# Sema.net
KiCad netlist of a schematic drawn in Altium Designer
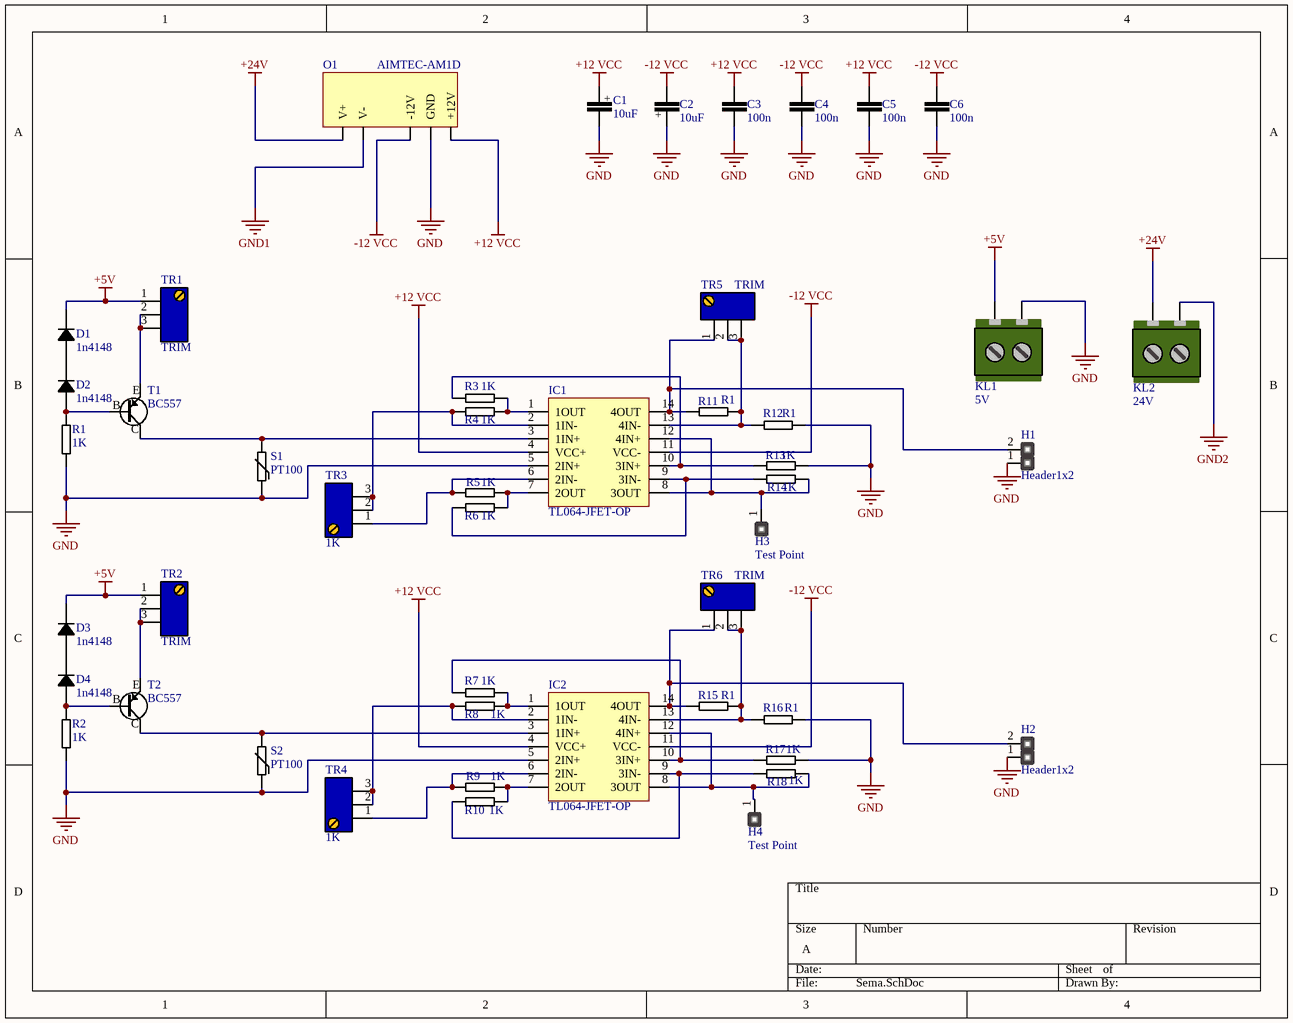
[diagram p0: Sema.SchDoc]

(export (version "E")
  (design (tool "Eeschema 10.0.6"))
  (components
    (comp (ref "C1") (value "10uF") (footprint "C2-Small") (libsource (lib "KILEX LIB SCH") (part "C2")))
    (comp (ref "C2") (value "10uF") (footprint "C2-Small") (libsource (lib "KILEX LIB SCH") (part "C2")))
    (comp (ref "C3")
      (value "100n")
      (footprint "C1(Ceramic)Small")
      (libsource (lib "KILEX LIB SCH") (part "C1"))
    )
    (comp (ref "C4")
      (value "100n")
      (footprint "C1(Ceramic)Small")
      (libsource (lib "KILEX LIB SCH") (part "C1"))
    )
    (comp (ref "C5")
      (value "100n")
      (footprint "C1(Ceramic)Small")
      (libsource (lib "KILEX LIB SCH") (part "C1"))
    )
    (comp (ref "C6")
      (value "100n")
      (footprint "C1(Ceramic)Small")
      (libsource (lib "KILEX LIB SCH") (part "C1"))
    )
    (comp (ref "D1")
      (value "1n4148")
      (footprint "D1(minimelf)")
      (libsource (lib "KILEX LIB SCH") (part "D1"))
    )
    (comp (ref "D2")
      (value "1n4148")
      (footprint "D1(minimelf)")
      (libsource (lib "KILEX LIB SCH") (part "D1"))
    )
    (comp (ref "D3")
      (value "1n4148")
      (footprint "D1(minimelf)")
      (libsource (lib "KILEX LIB SCH") (part "D1"))
    )
    (comp (ref "D4")
      (value "1n4148")
      (footprint "D1(minimelf)")
      (libsource (lib "KILEX LIB SCH") (part "D1"))
    )
    (comp (ref "H1")
      (value "Header1x2")
      (footprint "Header1x2")
      (libsource (lib "KILEX LIB SCH") (part "Header1x2"))
    )
    (comp (ref "H2")
      (value "Header1x2")
      (footprint "Header1x2")
      (libsource (lib "KILEX LIB SCH") (part "Header1x2"))
    )
    (comp (ref "H3") (value "Test Point") (footprint "H1x1") (libsource (lib "KILEX LIB SCH") (part "H1x1")))
    (comp (ref "H4") (value "Test Point") (footprint "H1x1") (libsource (lib "KILEX LIB SCH") (part "H1x1")))
    (comp (ref "IC1")
      (value "TL064-JFET-OP")
      (footprint "DIP14")
      (libsource (lib "KILEX LIB SCH") (part "TL064-JFET-OP"))
    )
    (comp (ref "IC2")
      (value "TL064-JFET-OP")
      (footprint "DIP14")
      (libsource (lib "KILEX LIB SCH") (part "TL064-JFET-OP"))
    )
    (comp (ref "KL1") (value "5V") (footprint "Klema") (libsource (lib "KILEX LIB SCH") (part "Klema")))
    (comp (ref "KL2") (value "24V") (footprint "Klema") (libsource (lib "KILEX LIB SCH") (part "Klema")))
    (comp (ref "O1")
      (value "AIMTEC-AM1D")
      (footprint "Aimtec-AM1D")
      (libsource (lib "KILEX LIB SCH") (part "AIMTEC-AM1D"))
    )
    (comp (ref "R1") (value "1K") (footprint "R 0805") (libsource (lib "KILEX LIB SCH") (part "R1")))
    (comp (ref "R2") (value "1K") (footprint "R 0805") (libsource (lib "KILEX LIB SCH") (part "R1")))
    (comp (ref "R3") (value "1K") (footprint "R 0805") (libsource (lib "KILEX LIB SCH") (part "R1")))
    (comp (ref "R4") (value "1K") (footprint "R 0805") (libsource (lib "KILEX LIB SCH") (part "R1")))
    (comp (ref "R5") (value "1K") (footprint "R 0805") (libsource (lib "KILEX LIB SCH") (part "R1")))
    (comp (ref "R6") (value "1K") (footprint "R 0805") (libsource (lib "KILEX LIB SCH") (part "R1")))
    (comp (ref "R7") (value "1K") (footprint "R 0805") (libsource (lib "KILEX LIB SCH") (part "R1")))
    (comp (ref "R8") (value "1K") (footprint "R 0805") (libsource (lib "KILEX LIB SCH") (part "R1")))
    (comp (ref "R9") (value "1K") (footprint "R 0805") (libsource (lib "KILEX LIB SCH") (part "R1")))
    (comp (ref "R10") (value "1K") (footprint "R 0805") (libsource (lib "KILEX LIB SCH") (part "R1")))
    (comp (ref "R11") (value "R1") (footprint "R 0805") (libsource (lib "KILEX LIB SCH") (part "R1")))
    (comp (ref "R12") (value "R1") (footprint "R 0805") (libsource (lib "KILEX LIB SCH") (part "R1")))
    (comp (ref "R13") (value "1K") (footprint "R 0805") (libsource (lib "KILEX LIB SCH") (part "R1")))
    (comp (ref "R14") (value "1K") (footprint "R 0805") (libsource (lib "KILEX LIB SCH") (part "R1")))
    (comp (ref "R15") (value "R1") (footprint "R 0805") (libsource (lib "KILEX LIB SCH") (part "R1")))
    (comp (ref "R16") (value "R1") (footprint "R 0805") (libsource (lib "KILEX LIB SCH") (part "R1")))
    (comp (ref "R17") (value "1K") (footprint "R 0805") (libsource (lib "KILEX LIB SCH") (part "R1")))
    (comp (ref "R18") (value "1K") (footprint "R 0805") (libsource (lib "KILEX LIB SCH") (part "R1")))
    (comp (ref "S1") (value "PT100") (footprint "Header1x2") (libsource (lib "KILEX LIB SCH") (part "PT100")))
    (comp (ref "S2") (value "PT100") (footprint "Header1x2") (libsource (lib "KILEX LIB SCH") (part "PT100")))
    (comp (ref "T1")
      (value "BC557")
      (footprint "sot23")
      (libsource (lib "KILEX LIB SCH") (part "Transistor PNP"))
    )
    (comp (ref "T2")
      (value "BC557")
      (footprint "sot23")
      (libsource (lib "KILEX LIB SCH") (part "Transistor PNP"))
    )
    (comp (ref "TR1") (value "TRIM") (footprint "TRIM") (libsource (lib "") (part "TRIM_1")))
    (comp (ref "TR2") (value "TRIM") (footprint "TRIM") (libsource (lib "") (part "TRIM_1")))
    (comp (ref "TR3") (value "1K") (footprint "TRIM") (libsource (lib "KILEX LIB SCH") (part "TRIM")))
    (comp (ref "TR4") (value "1K") (footprint "TRIM") (libsource (lib "KILEX LIB SCH") (part "TRIM")))
    (comp (ref "TR5") (value "TRIM") (footprint "TRIM") (libsource (lib "") (part "TRIM_2")))
    (comp (ref "TR6") (value "TRIM") (footprint "TRIM") (libsource (lib "") (part "TRIM_2")))
  )
  (nets
    (net (code "1") (name "+5V") (class "Default")
      (node (ref "D1") (pin "2") (pinfunction "2_2") (pintype "passive"))
      (node (ref "D3") (pin "2") (pinfunction "2_2") (pintype "passive"))
      (node (ref "KL1") (pin "2") (pinfunction "2_2") (pintype "passive"))
      (node (ref "TR1") (pin "1") (pinfunction "1_1") (pintype "passive"))
      (node (ref "TR2") (pin "1") (pinfunction "1_1") (pintype "passive"))
    )
    (net (code "2") (name "+12 VCC") (class "Default")
      (node (ref "C1") (pin "1") (pinfunction "1_1") (pintype "passive"))
      (node (ref "C3") (pin "2") (pinfunction "2_2") (pintype "passive"))
      (node (ref "C5") (pin "2") (pinfunction "2_2") (pintype "passive"))
      (node (ref "IC1") (pin "4") (pinfunction "VCC+_4") (pintype "passive"))
      (node (ref "IC2") (pin "4") (pinfunction "VCC+_4") (pintype "passive"))
      (node (ref "O1") (pin "5") (pinfunction "+12V_5") (pintype "passive"))
    )
    (net (code "3") (name "+24V") (class "Default")
      (node (ref "KL2") (pin "2") (pinfunction "2_2") (pintype "passive"))
      (node (ref "O1") (pin "1") (pinfunction "V+_1") (pintype "passive"))
    )
    (net (code "4") (name "-12 VCC") (class "Default")
      (node (ref "C2") (pin "2") (pinfunction "2_2") (pintype "passive"))
      (node (ref "C4") (pin "2") (pinfunction "2_2") (pintype "passive"))
      (node (ref "C6") (pin "2") (pinfunction "2_2") (pintype "passive"))
      (node (ref "IC1") (pin "11") (pinfunction "VCC-_11") (pintype "passive"))
      (node (ref "IC2") (pin "11") (pinfunction "VCC-_11") (pintype "passive"))
      (node (ref "O1") (pin "3") (pinfunction "-12V_3") (pintype "passive"))
    )
    (net (code "5") (name "GND") (class "Default")
      (node (ref "C1") (pin "2") (pinfunction "2_2") (pintype "passive"))
      (node (ref "C2") (pin "1") (pinfunction "1_1") (pintype "passive"))
      (node (ref "C3") (pin "1") (pinfunction "1_1") (pintype "passive"))
      (node (ref "C4") (pin "1") (pinfunction "1_1") (pintype "passive"))
      (node (ref "C5") (pin "1") (pinfunction "1_1") (pintype "passive"))
      (node (ref "C6") (pin "1") (pinfunction "1_1") (pintype "passive"))
      (node (ref "H1") (pin "1") (pinfunction "1_1") (pintype "passive"))
      (node (ref "H2") (pin "1") (pinfunction "1_1") (pintype "passive"))
      (node (ref "IC1") (pin "5") (pinfunction "2IN+_5") (pintype "passive"))
      (node (ref "IC2") (pin "5") (pinfunction "2IN+_5") (pintype "passive"))
      (node (ref "KL1") (pin "1") (pinfunction "1_1") (pintype "passive"))
      (node (ref "O1") (pin "4") (pinfunction "GND_4") (pintype "passive"))
      (node (ref "R1") (pin "1") (pinfunction "1_1") (pintype "passive"))
      (node (ref "R12") (pin "2") (pinfunction "2_2") (pintype "passive"))
      (node (ref "R13") (pin "1") (pinfunction "1_1") (pintype "passive"))
      (node (ref "R16") (pin "2") (pinfunction "2_2") (pintype "passive"))
      (node (ref "R17") (pin "1") (pinfunction "1_1") (pintype "passive"))
      (node (ref "R2") (pin "1") (pinfunction "1_1") (pintype "passive"))
      (node (ref "S1") (pin "2") (pinfunction "2_2") (pintype "passive"))
      (node (ref "S2") (pin "2") (pinfunction "2_2") (pintype "passive"))
    )
    (net (code "6") (name "GND1") (class "Default")
      (node (ref "O1") (pin "2") (pinfunction "V-_2") (pintype "passive"))
    )
    (net (code "7") (name "GND2") (class "Default")
      (node (ref "KL2") (pin "1") (pinfunction "1_1") (pintype "passive"))
    )
    (net (code "8") (name "Net-(D1-Pad1)") (class "Default")
      (node (ref "D1") (pin "1") (pinfunction "1_1") (pintype "passive"))
      (node (ref "D2") (pin "2") (pinfunction "2_2") (pintype "passive"))
    )
    (net (code "9") (name "Net-(D2-Pad1)") (class "Default")
      (node (ref "D2") (pin "1") (pinfunction "1_1") (pintype "passive"))
      (node (ref "R1") (pin "2") (pinfunction "2_2") (pintype "passive"))
      (node (ref "T1") (pin "1") (pinfunction "1_1") (pintype "passive"))
    )
    (net (code "10") (name "Net-(D3-Pad1)") (class "Default")
      (node (ref "D3") (pin "1") (pinfunction "1_1") (pintype "passive"))
      (node (ref "D4") (pin "2") (pinfunction "2_2") (pintype "passive"))
    )
    (net (code "11") (name "Net-(D4-Pad1)") (class "Default")
      (node (ref "D4") (pin "1") (pinfunction "1_1") (pintype "passive"))
      (node (ref "R2") (pin "2") (pinfunction "2_2") (pintype "passive"))
      (node (ref "T2") (pin "1") (pinfunction "1_1") (pintype "passive"))
    )
    (net (code "12") (name "Net-(IC1-1IN+)") (class "Default")
      (node (ref "IC1") (pin "3") (pinfunction "1IN+_3") (pintype "passive"))
      (node (ref "S1") (pin "1") (pinfunction "1_1") (pintype "passive"))
      (node (ref "T1") (pin "3") (pinfunction "3_3") (pintype "passive"))
    )
    (net (code "13") (name "Net-(IC1-1IN-)") (class "Default")
      (node (ref "IC1") (pin "2") (pinfunction "1IN-_2") (pintype "passive"))
      (node (ref "R4") (pin "2") (pinfunction "2_2") (pintype "passive"))
      (node (ref "TR3") (pin "2") (pinfunction "2_2") (pintype "passive"))
      (node (ref "TR3") (pin "3") (pinfunction "3_3") (pintype "passive"))
    )
    (net (code "14") (name "Net-(IC1-1OUT)") (class "Default")
      (node (ref "IC1") (pin "1") (pinfunction "1OUT_1") (pintype "passive"))
      (node (ref "R3") (pin "2") (pinfunction "2_2") (pintype "passive"))
      (node (ref "R4") (pin "1") (pinfunction "1_1") (pintype "passive"))
    )
    (net (code "15") (name "Net-(IC1-2IN-)") (class "Default")
      (node (ref "IC1") (pin "6") (pinfunction "2IN-_6") (pintype "passive"))
      (node (ref "R5") (pin "1") (pinfunction "1_1") (pintype "passive"))
      (node (ref "TR3") (pin "1") (pinfunction "1_1") (pintype "passive"))
    )
    (net (code "16") (name "Net-(IC1-2OUT)") (class "Default")
      (node (ref "IC1") (pin "7") (pinfunction "2OUT_7") (pintype "passive"))
      (node (ref "R5") (pin "2") (pinfunction "2_2") (pintype "passive"))
      (node (ref "R6") (pin "1") (pinfunction "1_1") (pintype "passive"))
    )
    (net (code "17") (name "Net-(IC1-3IN+)") (class "Default")
      (node (ref "IC1") (pin "10") (pinfunction "3IN+_10") (pintype "passive"))
      (node (ref "R13") (pin "2") (pinfunction "2_2") (pintype "passive"))
      (node (ref "R3") (pin "1") (pinfunction "1_1") (pintype "passive"))
    )
    (net (code "18") (name "Net-(IC1-3IN-)") (class "Default")
      (node (ref "IC1") (pin "9") (pinfunction "3IN-_9") (pintype "passive"))
      (node (ref "R14") (pin "1") (pinfunction "1_1") (pintype "passive"))
      (node (ref "R6") (pin "2") (pinfunction "2_2") (pintype "passive"))
    )
    (net (code "19") (name "Net-(IC1-3OUT)") (class "Default")
      (node (ref "H3") (pin "1") (pinfunction "1_1") (pintype "passive"))
      (node (ref "IC1") (pin "12") (pinfunction "4IN+_12") (pintype "passive"))
      (node (ref "IC1") (pin "8") (pinfunction "3OUT_8") (pintype "passive"))
      (node (ref "R14") (pin "2") (pinfunction "2_2") (pintype "passive"))
    )
    (net (code "20") (name "Net-(IC1-4IN-)") (class "Default")
      (node (ref "IC1") (pin "13") (pinfunction "4IN-_13") (pintype "passive"))
      (node (ref "R11") (pin "2") (pinfunction "2_2") (pintype "passive"))
      (node (ref "R12") (pin "1") (pinfunction "1_1") (pintype "passive"))
      (node (ref "TR5") (pin "2") (pinfunction "2_2") (pintype "passive"))
      (node (ref "TR5") (pin "3") (pinfunction "3_3") (pintype "passive"))
    )
    (net (code "21") (name "Net-(IC1-4OUT)") (class "Default")
      (node (ref "H1") (pin "2") (pinfunction "2_2") (pintype "passive"))
      (node (ref "IC1") (pin "14") (pinfunction "4OUT_14") (pintype "passive"))
      (node (ref "R11") (pin "1") (pinfunction "1_1") (pintype "passive"))
      (node (ref "TR5") (pin "1") (pinfunction "1_1") (pintype "passive"))
    )
    (net (code "22") (name "Net-(IC2-1IN+)") (class "Default")
      (node (ref "IC2") (pin "3") (pinfunction "1IN+_3") (pintype "passive"))
      (node (ref "S2") (pin "1") (pinfunction "1_1") (pintype "passive"))
      (node (ref "T2") (pin "3") (pinfunction "3_3") (pintype "passive"))
    )
    (net (code "23") (name "Net-(IC2-1IN-)") (class "Default")
      (node (ref "IC2") (pin "2") (pinfunction "1IN-_2") (pintype "passive"))
      (node (ref "R8") (pin "2") (pinfunction "2_2") (pintype "passive"))
      (node (ref "TR4") (pin "2") (pinfunction "2_2") (pintype "passive"))
      (node (ref "TR4") (pin "3") (pinfunction "3_3") (pintype "passive"))
    )
    (net (code "24") (name "Net-(IC2-1OUT)") (class "Default")
      (node (ref "IC2") (pin "1") (pinfunction "1OUT_1") (pintype "passive"))
      (node (ref "R7") (pin "2") (pinfunction "2_2") (pintype "passive"))
      (node (ref "R8") (pin "1") (pinfunction "1_1") (pintype "passive"))
    )
    (net (code "25") (name "Net-(IC2-2IN-)") (class "Default")
      (node (ref "IC2") (pin "6") (pinfunction "2IN-_6") (pintype "passive"))
      (node (ref "R9") (pin "1") (pinfunction "1_1") (pintype "passive"))
      (node (ref "TR4") (pin "1") (pinfunction "1_1") (pintype "passive"))
    )
    (net (code "26") (name "Net-(IC2-2OUT)") (class "Default")
      (node (ref "IC2") (pin "7") (pinfunction "2OUT_7") (pintype "passive"))
      (node (ref "R10") (pin "1") (pinfunction "1_1") (pintype "passive"))
      (node (ref "R9") (pin "2") (pinfunction "2_2") (pintype "passive"))
    )
    (net (code "27") (name "Net-(IC2-3IN+)") (class "Default")
      (node (ref "IC2") (pin "10") (pinfunction "3IN+_10") (pintype "passive"))
      (node (ref "R17") (pin "2") (pinfunction "2_2") (pintype "passive"))
      (node (ref "R7") (pin "1") (pinfunction "1_1") (pintype "passive"))
    )
    (net (code "28") (name "Net-(IC2-3IN-)") (class "Default")
      (node (ref "IC2") (pin "9") (pinfunction "3IN-_9") (pintype "passive"))
      (node (ref "R10") (pin "2") (pinfunction "2_2") (pintype "passive"))
      (node (ref "R18") (pin "1") (pinfunction "1_1") (pintype "passive"))
    )
    (net (code "29") (name "Net-(IC2-3OUT)") (class "Default")
      (node (ref "H4") (pin "1") (pinfunction "1_1") (pintype "passive"))
      (node (ref "IC2") (pin "12") (pinfunction "4IN+_12") (pintype "passive"))
      (node (ref "IC2") (pin "8") (pinfunction "3OUT_8") (pintype "passive"))
      (node (ref "R18") (pin "2") (pinfunction "2_2") (pintype "passive"))
    )
    (net (code "30") (name "Net-(IC2-4IN-)") (class "Default")
      (node (ref "IC2") (pin "13") (pinfunction "4IN-_13") (pintype "passive"))
      (node (ref "R15") (pin "2") (pinfunction "2_2") (pintype "passive"))
      (node (ref "R16") (pin "1") (pinfunction "1_1") (pintype "passive"))
      (node (ref "TR6") (pin "2") (pinfunction "2_2") (pintype "passive"))
      (node (ref "TR6") (pin "3") (pinfunction "3_3") (pintype "passive"))
    )
    (net (code "31") (name "Net-(IC2-4OUT)") (class "Default")
      (node (ref "H2") (pin "2") (pinfunction "2_2") (pintype "passive"))
      (node (ref "IC2") (pin "14") (pinfunction "4OUT_14") (pintype "passive"))
      (node (ref "R15") (pin "1") (pinfunction "1_1") (pintype "passive"))
      (node (ref "TR6") (pin "1") (pinfunction "1_1") (pintype "passive"))
    )
    (net (code "32") (name "Net-(T1-Pad2)") (class "Default")
      (node (ref "T1") (pin "2") (pinfunction "2_2") (pintype "passive"))
      (node (ref "TR1") (pin "2") (pinfunction "2_2") (pintype "passive"))
      (node (ref "TR1") (pin "3") (pinfunction "3_3") (pintype "passive"))
    )
    (net (code "33") (name "Net-(T2-Pad2)") (class "Default")
      (node (ref "T2") (pin "2") (pinfunction "2_2") (pintype "passive"))
      (node (ref "TR2") (pin "2") (pinfunction "2_2") (pintype "passive"))
      (node (ref "TR2") (pin "3") (pinfunction "3_3") (pintype "passive"))
    )
  )
)
